# I-Ching_Device_overview_EasyEDA.net
KiCad netlist of a schematic drawn in EasyEDA
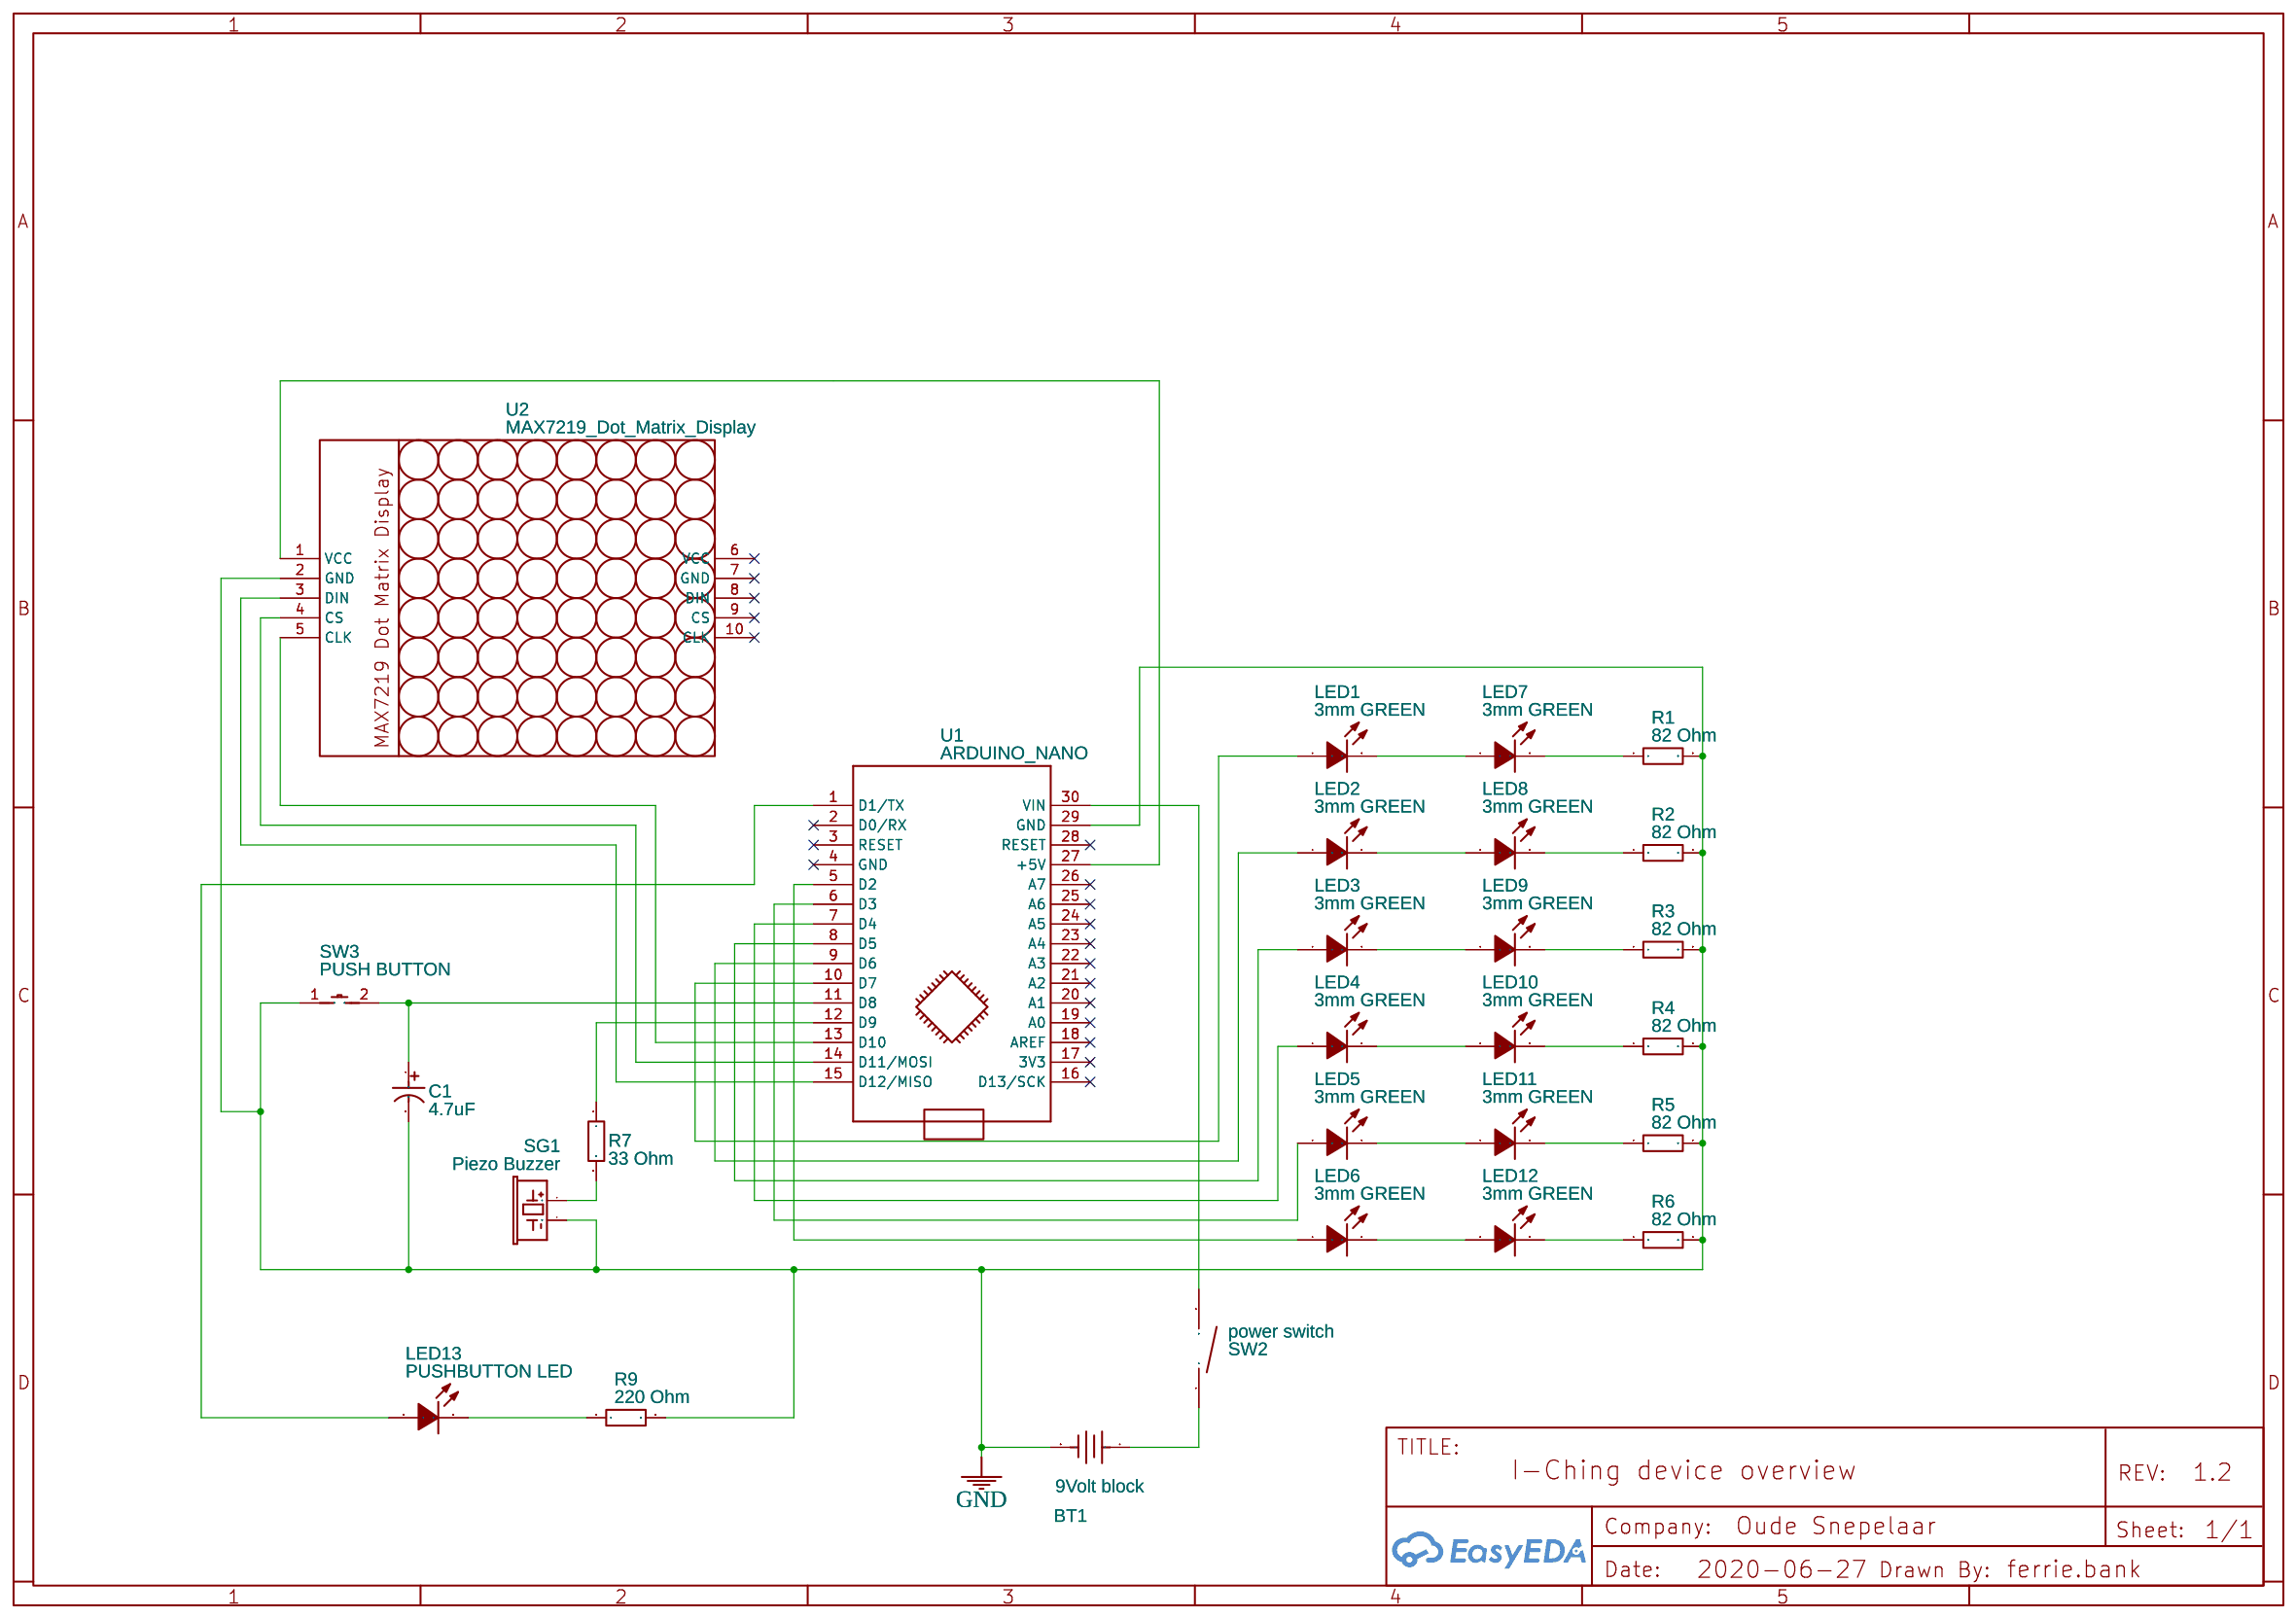
[diagram p0: schematic sheet]

(export (version "E")
  (design (tool "Eeschema 10.0.6"))
  (components
    (comp (ref "BT1")
      (value "9Volt block")
      (fields (field (name "BOM_Manufacturer Part") "1067") (field (name "BOM_Supplier Part") "C238072"))
      (libsource (lib "") (part "1067"))
    )
    (comp (ref "C1")
      (value "4.7uF")
      (fields (field (name "BOM_Manufacturer Part") "0.1UF 50V") (field (name "BOM_Supplier Part") "C28061"))
      (libsource (lib "") (part "0.1UF 50V"))
    )
    (comp (ref "LED1")
      (value "3mm GREEN")
      (fields (field (name "BOM_Manufacturer Part") "3ARG4HWC") (field (name "BOM_Supplier Part") "C55640"))
      (libsource (lib "") (part "3ARG4HWC"))
    )
    (comp (ref "LED2")
      (value "3mm GREEN")
      (fields (field (name "BOM_Manufacturer Part") "3ARG4HWC") (field (name "BOM_Supplier Part") "C55640"))
      (libsource (lib "") (part "3ARG4HWC"))
    )
    (comp (ref "LED3")
      (value "3mm GREEN")
      (fields (field (name "BOM_Manufacturer Part") "3ARG4HWC") (field (name "BOM_Supplier Part") "C55640"))
      (libsource (lib "") (part "3ARG4HWC"))
    )
    (comp (ref "LED4")
      (value "3mm GREEN")
      (fields (field (name "BOM_Manufacturer Part") "3ARG4HWC") (field (name "BOM_Supplier Part") "C55640"))
      (libsource (lib "") (part "3ARG4HWC"))
    )
    (comp (ref "LED5")
      (value "3mm GREEN")
      (fields (field (name "BOM_Manufacturer Part") "3ARG4HWC") (field (name "BOM_Supplier Part") "C55640"))
      (libsource (lib "") (part "3ARG4HWC"))
    )
    (comp (ref "LED6")
      (value "3mm GREEN")
      (fields (field (name "BOM_Manufacturer Part") "3ARG4HWC") (field (name "BOM_Supplier Part") "C55640"))
      (libsource (lib "") (part "3ARG4HWC"))
    )
    (comp (ref "LED7")
      (value "3mm GREEN")
      (fields (field (name "BOM_Manufacturer Part") "3ARG4HWC") (field (name "BOM_Supplier Part") "C55640"))
      (libsource (lib "") (part "3ARG4HWC"))
    )
    (comp (ref "LED8")
      (value "3mm GREEN")
      (fields (field (name "BOM_Manufacturer Part") "3ARG4HWC") (field (name "BOM_Supplier Part") "C55640"))
      (libsource (lib "") (part "3ARG4HWC"))
    )
    (comp (ref "LED9")
      (value "3mm GREEN")
      (fields (field (name "BOM_Manufacturer Part") "3ARG4HWC") (field (name "BOM_Supplier Part") "C55640"))
      (libsource (lib "") (part "3ARG4HWC"))
    )
    (comp (ref "LED10")
      (value "3mm GREEN")
      (fields (field (name "BOM_Manufacturer Part") "3ARG4HWC") (field (name "BOM_Supplier Part") "C55640"))
      (libsource (lib "") (part "3ARG4HWC"))
    )
    (comp (ref "LED11")
      (value "3mm GREEN")
      (fields (field (name "BOM_Manufacturer Part") "3ARG4HWC") (field (name "BOM_Supplier Part") "C55640"))
      (libsource (lib "") (part "3ARG4HWC"))
    )
    (comp (ref "LED12")
      (value "3mm GREEN")
      (fields (field (name "BOM_Manufacturer Part") "3ARG4HWC") (field (name "BOM_Supplier Part") "C55640"))
      (libsource (lib "") (part "3ARG4HWC"))
    )
    (comp (ref "LED13")
      (value "PUSHBUTTON LED")
      (fields (field (name "BOM_Manufacturer Part") "3ARG4HWC") (field (name "BOM_Supplier Part") "C55640"))
      (libsource (lib "") (part "3ARG4HWC"))
    )
    (comp (ref "R1")
      (value "82 Ohm")
      (fields
        (field (name "BOM_Manufacturer Part") "MFR2WSJT-73-220R")
        (field (name "BOM_Supplier Part") "C176568")
      )
      (libsource (lib "") (part "MFR2WSJT-73-220R"))
    )
    (comp (ref "R2")
      (value "82 Ohm")
      (fields
        (field (name "BOM_Manufacturer Part") "MFR2WSJT-73-220R")
        (field (name "BOM_Supplier Part") "C176568")
      )
      (libsource (lib "") (part "MFR2WSJT-73-220R"))
    )
    (comp (ref "R3")
      (value "82 Ohm")
      (fields
        (field (name "BOM_Manufacturer Part") "MFR2WSJT-73-220R")
        (field (name "BOM_Supplier Part") "C176568")
      )
      (libsource (lib "") (part "MFR2WSJT-73-220R"))
    )
    (comp (ref "R4")
      (value "82 Ohm")
      (fields
        (field (name "BOM_Manufacturer Part") "MFR2WSJT-73-220R")
        (field (name "BOM_Supplier Part") "C176568")
      )
      (libsource (lib "") (part "MFR2WSJT-73-220R"))
    )
    (comp (ref "R5")
      (value "82 Ohm")
      (fields
        (field (name "BOM_Manufacturer Part") "MFR2WSJT-73-220R")
        (field (name "BOM_Supplier Part") "C176568")
      )
      (libsource (lib "") (part "MFR2WSJT-73-220R"))
    )
    (comp (ref "R6")
      (value "82 Ohm")
      (fields
        (field (name "BOM_Manufacturer Part") "MFR2WSJT-73-220R")
        (field (name "BOM_Supplier Part") "C176568")
      )
      (libsource (lib "") (part "MFR2WSJT-73-220R"))
    )
    (comp (ref "R7")
      (value "33 Ohm")
      (fields
        (field (name "BOM_Manufacturer Part") "MFR2WSJT-73-220R")
        (field (name "BOM_Supplier Part") "C176568")
      )
      (libsource (lib "") (part "MFR2WSJT-73-220R_1"))
    )
    (comp (ref "R9")
      (value "220 Ohm")
      (fields
        (field (name "BOM_Manufacturer Part") "MFR2WSJT-73-220R")
        (field (name "BOM_Supplier Part") "C176568")
      )
      (libsource (lib "") (part "MFR2WSJT-73-220R"))
    )
    (comp (ref "SG1") (value "Piezo Buzzer") (libsource (lib "") (part "Piezo Buzzer")))
    (comp (ref "SW2")
      (value "power switch")
      (fields
        (field (name "BOM_Manufacturer Part") "SS11-RBDWQ-R20-R")
        (field (name "BOM_Supplier Part") "C309068")
      )
      (libsource (lib "") (part "SS11-RBDWQ-R20-R"))
    )
    (comp (ref "SW3")
      (value "PUSH BUTTON")
      (fields
        (field (name "BOM_Manufacturer Part") "SKTQABE010")
        (field (name "BOM_Supplier Part") "C470454")
      )
      (libsource (lib "") (part "SKTQABE010"))
    )
    (comp (ref "U1") (value "ARDUINO_NANO") (libsource (lib "") (part "ARDUINO_NANO")))
    (comp (ref "U2")
      (value "MAX7219_Dot_Matrix_Display")
      (libsource (lib "") (part "MAX7219_Dot_Matrix_Display"))
    )
  )
  (nets
    (net (code "1") (name "GND") (class "Default")
      (node (ref "BT1") (pin "2") (pinfunction "-_2") (pintype "unspecified"))
      (node (ref "C1") (pin "2") (pinfunction "2_2") (pintype "input"))
      (node (ref "R1") (pin "2") (pinfunction "2_2") (pintype "input"))
      (node (ref "R2") (pin "2") (pinfunction "2_2") (pintype "input"))
      (node (ref "R3") (pin "2") (pinfunction "2_2") (pintype "input"))
      (node (ref "R4") (pin "2") (pinfunction "2_2") (pintype "input"))
      (node (ref "R5") (pin "2") (pinfunction "2_2") (pintype "input"))
      (node (ref "R6") (pin "2") (pinfunction "2_2") (pintype "input"))
      (node (ref "R9") (pin "2") (pinfunction "2_2") (pintype "input"))
      (node (ref "SG1") (pin "-") (pinfunction "2_-") (pintype "unspecified"))
      (node (ref "SW3") (pin "1") (pinfunction "1_1") (pintype "unspecified"))
      (node (ref "U1") (pin "29") (pinfunction "GND_29") (pintype "unspecified"))
      (node (ref "U2") (pin "2") (pinfunction "GND_2") (pintype "unspecified"))
    )
    (net (code "2") (name "Net-(BT1-+)") (class "Default")
      (node (ref "BT1") (pin "1") (pinfunction "+_1") (pintype "unspecified"))
      (node (ref "SW2") (pin "1") (pinfunction "1_1") (pintype "input"))
    )
    (net (code "3") (name "Net-(LED1-A)") (class "Default")
      (node (ref "LED1") (pin "1") (pinfunction "A_1") (pintype "unspecified"))
      (node (ref "U1") (pin "10") (pinfunction "D7_10") (pintype "unspecified"))
    )
    (net (code "4") (name "Net-(LED1-K)") (class "Default")
      (node (ref "LED1") (pin "2") (pinfunction "K_2") (pintype "unspecified"))
      (node (ref "LED7") (pin "1") (pinfunction "A_1") (pintype "unspecified"))
    )
    (net (code "5") (name "Net-(LED2-A)") (class "Default")
      (node (ref "LED2") (pin "1") (pinfunction "A_1") (pintype "unspecified"))
      (node (ref "U1") (pin "9") (pinfunction "D6_9") (pintype "unspecified"))
    )
    (net (code "6") (name "Net-(LED2-K)") (class "Default")
      (node (ref "LED2") (pin "2") (pinfunction "K_2") (pintype "unspecified"))
      (node (ref "LED8") (pin "1") (pinfunction "A_1") (pintype "unspecified"))
    )
    (net (code "7") (name "Net-(LED3-A)") (class "Default")
      (node (ref "LED3") (pin "1") (pinfunction "A_1") (pintype "unspecified"))
      (node (ref "U1") (pin "8") (pinfunction "D5_8") (pintype "unspecified"))
    )
    (net (code "8") (name "Net-(LED3-K)") (class "Default")
      (node (ref "LED3") (pin "2") (pinfunction "K_2") (pintype "unspecified"))
      (node (ref "LED9") (pin "1") (pinfunction "A_1") (pintype "unspecified"))
    )
    (net (code "9") (name "Net-(LED4-A)") (class "Default")
      (node (ref "LED4") (pin "1") (pinfunction "A_1") (pintype "unspecified"))
      (node (ref "U1") (pin "7") (pinfunction "D4_7") (pintype "unspecified"))
    )
    (net (code "10") (name "Net-(LED5-A)") (class "Default")
      (node (ref "LED5") (pin "1") (pinfunction "A_1") (pintype "unspecified"))
      (node (ref "U1") (pin "6") (pinfunction "D3_6") (pintype "unspecified"))
    )
    (net (code "11") (name "Net-(LED6-A)") (class "Default")
      (node (ref "LED6") (pin "1") (pinfunction "A_1") (pintype "unspecified"))
      (node (ref "U1") (pin "5") (pinfunction "D2_5") (pintype "unspecified"))
    )
    (net (code "12") (name "Net-(LED7-K)") (class "Default")
      (node (ref "LED7") (pin "2") (pinfunction "K_2") (pintype "unspecified"))
      (node (ref "R1") (pin "1") (pinfunction "1_1") (pintype "input"))
    )
    (net (code "13") (name "Net-(LED8-K)") (class "Default")
      (node (ref "LED8") (pin "2") (pinfunction "K_2") (pintype "unspecified"))
      (node (ref "R2") (pin "1") (pinfunction "1_1") (pintype "input"))
    )
    (net (code "14") (name "Net-(LED9-K)") (class "Default")
      (node (ref "LED9") (pin "2") (pinfunction "K_2") (pintype "unspecified"))
      (node (ref "R3") (pin "1") (pinfunction "1_1") (pintype "input"))
    )
    (net (code "15") (name "Net-(LED10-A)") (class "Default")
      (node (ref "LED10") (pin "1") (pinfunction "A_1") (pintype "unspecified"))
      (node (ref "LED4") (pin "2") (pinfunction "K_2") (pintype "unspecified"))
    )
    (net (code "16") (name "Net-(LED10-K)") (class "Default")
      (node (ref "LED10") (pin "2") (pinfunction "K_2") (pintype "unspecified"))
      (node (ref "R4") (pin "1") (pinfunction "1_1") (pintype "input"))
    )
    (net (code "17") (name "Net-(LED11-A)") (class "Default")
      (node (ref "LED11") (pin "1") (pinfunction "A_1") (pintype "unspecified"))
      (node (ref "LED5") (pin "2") (pinfunction "K_2") (pintype "unspecified"))
    )
    (net (code "18") (name "Net-(LED11-K)") (class "Default")
      (node (ref "LED11") (pin "2") (pinfunction "K_2") (pintype "unspecified"))
      (node (ref "R5") (pin "1") (pinfunction "1_1") (pintype "input"))
    )
    (net (code "19") (name "Net-(LED12-A)") (class "Default")
      (node (ref "LED12") (pin "1") (pinfunction "A_1") (pintype "unspecified"))
      (node (ref "LED6") (pin "2") (pinfunction "K_2") (pintype "unspecified"))
    )
    (net (code "20") (name "Net-(LED12-K)") (class "Default")
      (node (ref "LED12") (pin "2") (pinfunction "K_2") (pintype "unspecified"))
      (node (ref "R6") (pin "1") (pinfunction "1_1") (pintype "input"))
    )
    (net (code "21") (name "Net-(LED13-A)") (class "Default")
      (node (ref "LED13") (pin "1") (pinfunction "A_1") (pintype "unspecified"))
      (node (ref "U1") (pin "1") (pinfunction "D1/TX_1") (pintype "unspecified"))
    )
    (net (code "22") (name "Net-(LED13-K)") (class "Default")
      (node (ref "LED13") (pin "2") (pinfunction "K_2") (pintype "unspecified"))
      (node (ref "R9") (pin "1") (pinfunction "1_1") (pintype "input"))
    )
    (net (code "23") (name "Net-(SG1-1)") (class "Default")
      (node (ref "R7") (pin "2") (pinfunction "2_2") (pintype "input"))
      (node (ref "SG1") (pin "+") (pinfunction "1_+") (pintype "unspecified"))
    )
    (net (code "24") (name "Net-(U1-+5V)") (class "Default")
      (node (ref "U1") (pin "27") (pinfunction "+5V_27") (pintype "unspecified"))
      (node (ref "U2") (pin "1") (pinfunction "VCC_1") (pintype "unspecified"))
    )
    (net (code "25") (name "Net-(U1-D8)") (class "Default")
      (node (ref "C1") (pin "1") (pinfunction "1_1") (pintype "input"))
      (node (ref "SW3") (pin "2") (pinfunction "2_2") (pintype "unspecified"))
      (node (ref "U1") (pin "11") (pinfunction "D8_11") (pintype "unspecified"))
    )
    (net (code "26") (name "Net-(U1-D9)") (class "Default")
      (node (ref "R7") (pin "1") (pinfunction "1_1") (pintype "input"))
      (node (ref "U1") (pin "12") (pinfunction "D9_12") (pintype "unspecified"))
    )
    (net (code "27") (name "Net-(U1-D10)") (class "Default")
      (node (ref "U1") (pin "13") (pinfunction "D10_13") (pintype "unspecified"))
      (node (ref "U2") (pin "5") (pinfunction "CLK_5") (pintype "unspecified"))
    )
    (net (code "28") (name "Net-(U1-D11{slash}MOSI)") (class "Default")
      (node (ref "U1") (pin "14") (pinfunction "D11/MOSI_14") (pintype "unspecified"))
      (node (ref "U2") (pin "4") (pinfunction "CS_4") (pintype "unspecified"))
    )
    (net (code "29") (name "Net-(U1-D12{slash}MISO)") (class "Default")
      (node (ref "U1") (pin "15") (pinfunction "D12/MISO_15") (pintype "unspecified"))
      (node (ref "U2") (pin "3") (pinfunction "DIN_3") (pintype "unspecified"))
    )
    (net (code "30") (name "Net-(U1-VIN)") (class "Default")
      (node (ref "SW2") (pin "2") (pinfunction "2_2") (pintype "input"))
      (node (ref "U1") (pin "30") (pinfunction "VIN_30") (pintype "unspecified"))
    )
    (net (code "31") (name "unconnected-(U1-3V3-Pad17)") (class "Default")
      (node (ref "U1") (pin "17") (pinfunction "3V3_17") (pintype "unspecified+no_connect"))
    )
    (net (code "32") (name "unconnected-(U1-A0-Pad19)") (class "Default")
      (node (ref "U1") (pin "19") (pinfunction "A0_19") (pintype "unspecified+no_connect"))
    )
    (net (code "33") (name "unconnected-(U1-A1-Pad20)") (class "Default")
      (node (ref "U1") (pin "20") (pinfunction "A1_20") (pintype "unspecified+no_connect"))
    )
    (net (code "34") (name "unconnected-(U1-A2-Pad21)") (class "Default")
      (node (ref "U1") (pin "21") (pinfunction "A2_21") (pintype "unspecified+no_connect"))
    )
    (net (code "35") (name "unconnected-(U1-A3-Pad22)") (class "Default")
      (node (ref "U1") (pin "22") (pinfunction "A3_22") (pintype "unspecified+no_connect"))
    )
    (net (code "36") (name "unconnected-(U1-A4-Pad23)") (class "Default")
      (node (ref "U1") (pin "23") (pinfunction "A4_23") (pintype "unspecified+no_connect"))
    )
    (net (code "37") (name "unconnected-(U1-A5-Pad24)") (class "Default")
      (node (ref "U1") (pin "24") (pinfunction "A5_24") (pintype "unspecified+no_connect"))
    )
    (net (code "38") (name "unconnected-(U1-A6-Pad25)") (class "Default")
      (node (ref "U1") (pin "25") (pinfunction "A6_25") (pintype "unspecified+no_connect"))
    )
    (net (code "39") (name "unconnected-(U1-A7-Pad26)") (class "Default")
      (node (ref "U1") (pin "26") (pinfunction "A7_26") (pintype "unspecified+no_connect"))
    )
    (net (code "40") (name "unconnected-(U1-AREF-Pad18)") (class "Default")
      (node (ref "U1") (pin "18") (pinfunction "AREF_18") (pintype "unspecified+no_connect"))
    )
    (net (code "41") (name "unconnected-(U1-D0{slash}RX-Pad2)") (class "Default")
      (node (ref "U1") (pin "2") (pinfunction "D0/RX_2") (pintype "unspecified+no_connect"))
    )
    (net (code "42") (name "unconnected-(U1-D13{slash}SCK-Pad16)") (class "Default")
      (node (ref "U1") (pin "16") (pinfunction "D13/SCK_16") (pintype "unspecified+no_connect"))
    )
    (net (code "43") (name "unconnected-(U1-GND-Pad4)") (class "Default")
      (node (ref "U1") (pin "4") (pinfunction "GND_4") (pintype "unspecified+no_connect"))
    )
    (net (code "44") (name "unconnected-(U1-RESET-Pad3)") (class "Default")
      (node (ref "U1") (pin "3") (pinfunction "RESET_3") (pintype "unspecified+no_connect"))
    )
    (net (code "45") (name "unconnected-(U1-RESET-Pad28)") (class "Default")
      (node (ref "U1") (pin "28") (pinfunction "RESET_28") (pintype "unspecified+no_connect"))
    )
    (net (code "46") (name "unconnected-(U2-CLK-Pad10)") (class "Default")
      (node (ref "U2") (pin "10") (pinfunction "CLK_10") (pintype "unspecified+no_connect"))
    )
    (net (code "47") (name "unconnected-(U2-CS-Pad9)") (class "Default")
      (node (ref "U2") (pin "9") (pinfunction "CS_9") (pintype "unspecified+no_connect"))
    )
    (net (code "48") (name "unconnected-(U2-DIN-Pad8)") (class "Default")
      (node (ref "U2") (pin "8") (pinfunction "DIN_8") (pintype "unspecified+no_connect"))
    )
    (net (code "49") (name "unconnected-(U2-GND-Pad7)") (class "Default")
      (node (ref "U2") (pin "7") (pinfunction "GND_7") (pintype "unspecified+no_connect"))
    )
    (net (code "50") (name "unconnected-(U2-VCC-Pad6)") (class "Default")
      (node (ref "U2") (pin "6") (pinfunction "VCC_6") (pintype "unspecified+no_connect"))
    )
  )
)
